# Snare.net
KiCad netlist of a schematic drawn in EAGLE
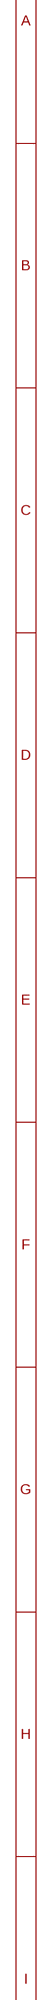
[diagram p0: schematic, sheet 1, part 1 of 2]
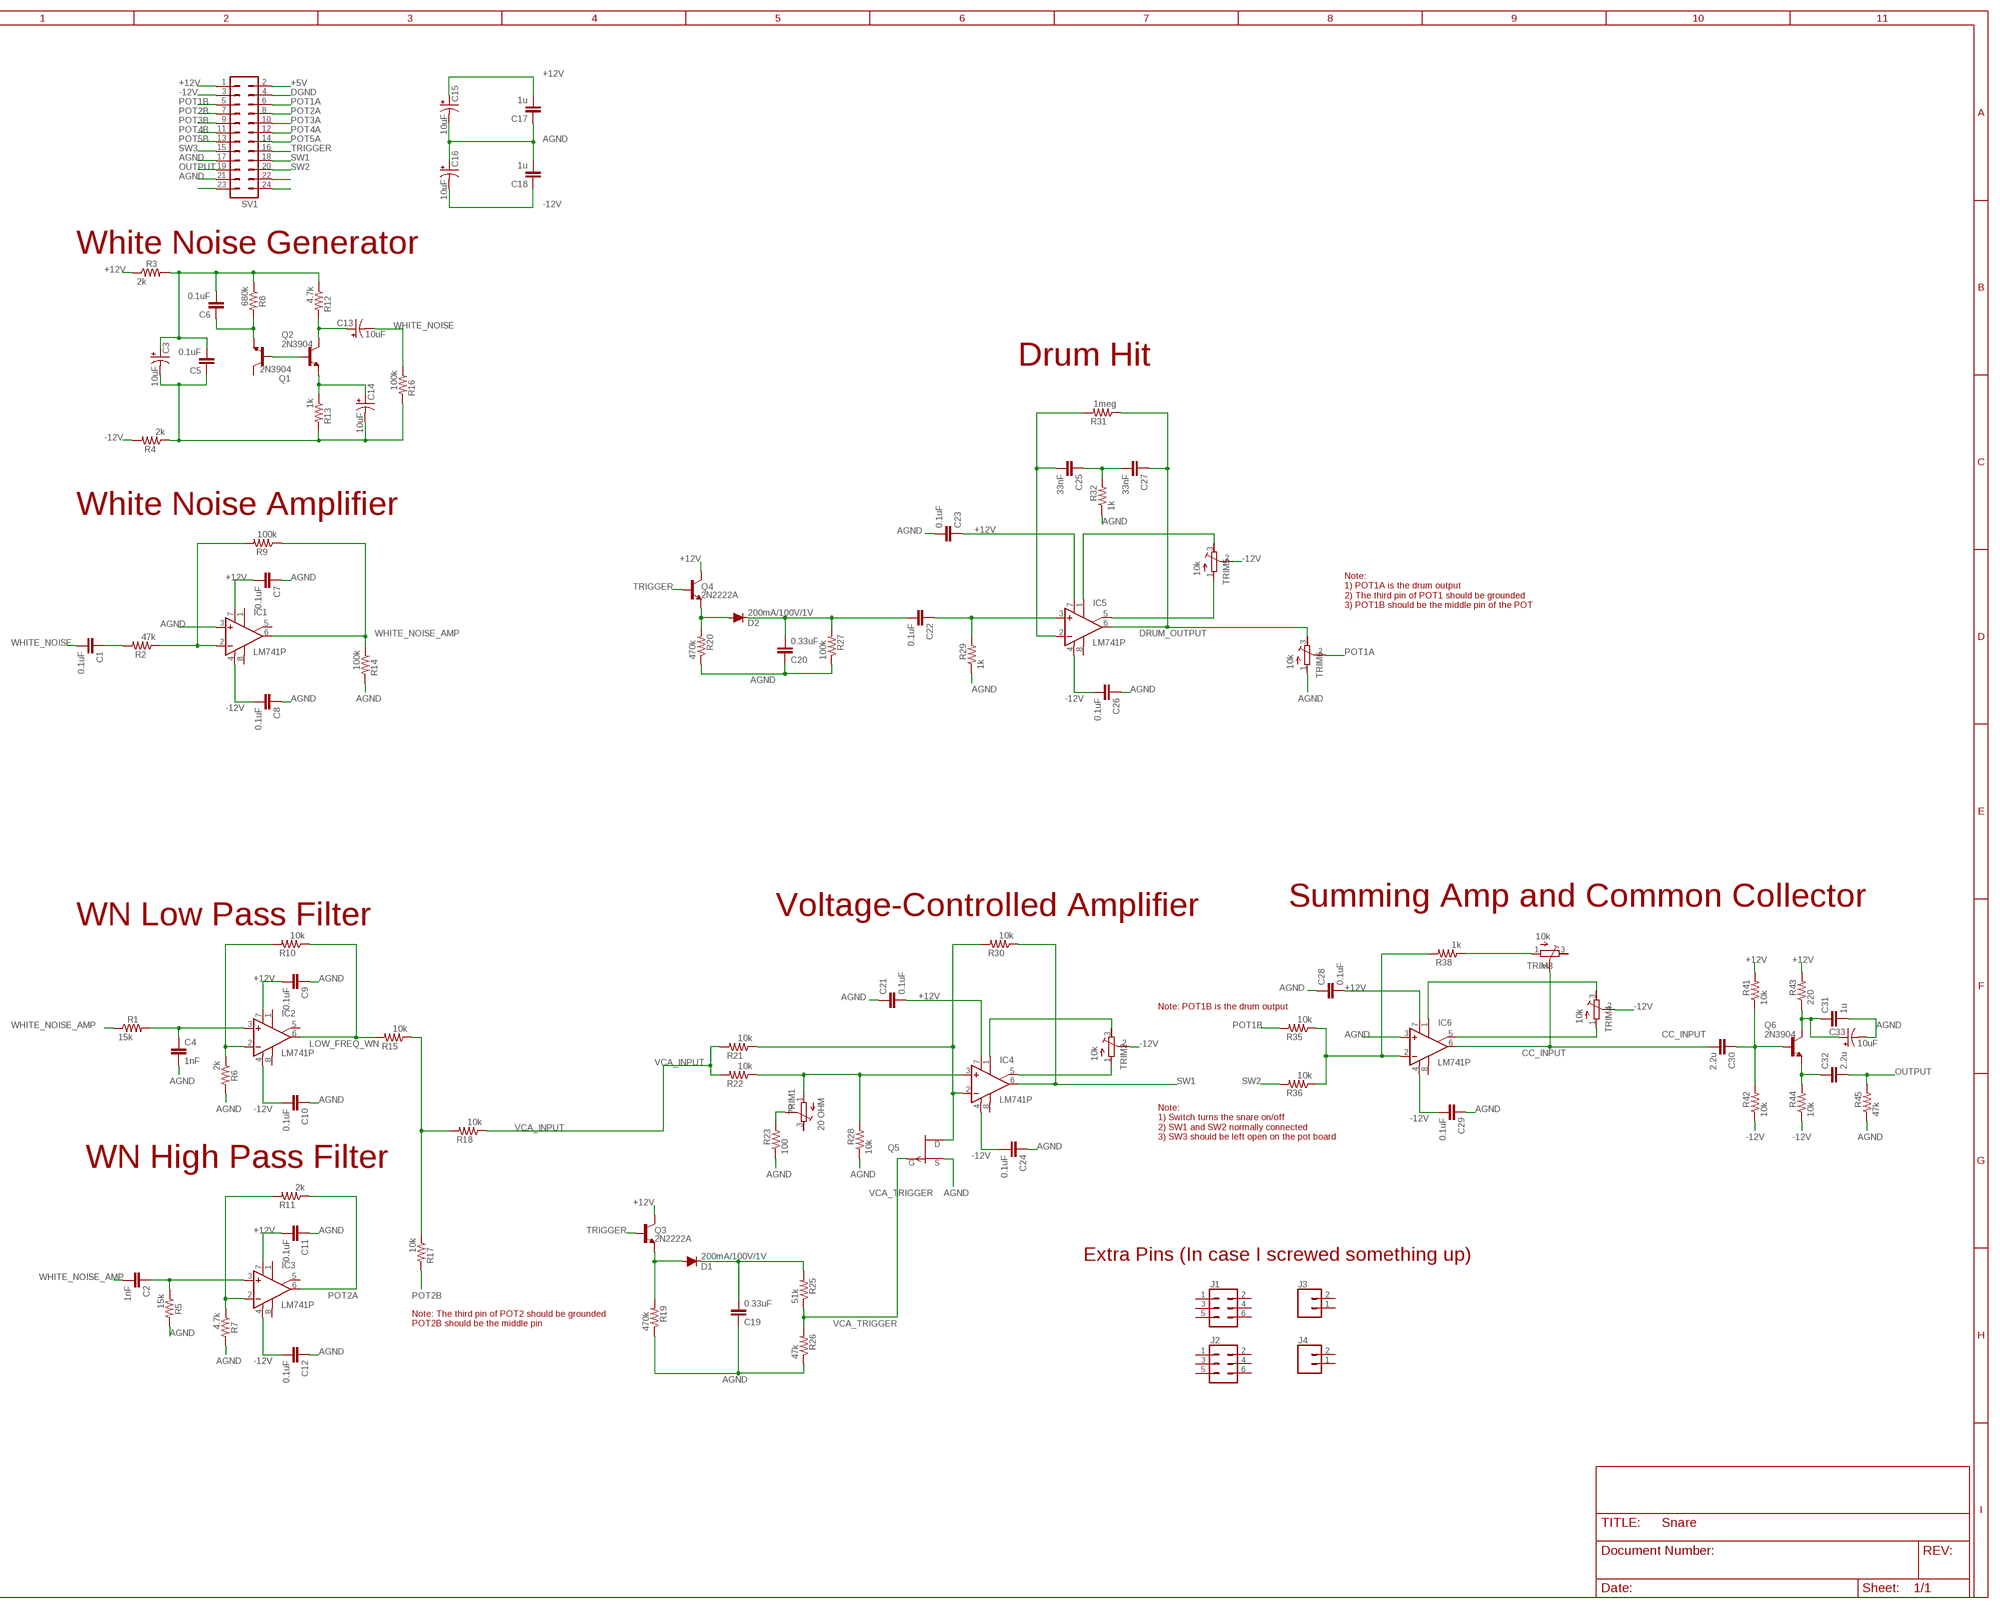
[diagram p1: schematic, sheet 1, part 2 of 2]

(export (version "E")
  (design (tool "Eeschema 10.0.6"))
  (components
    (comp (ref "C1")
      (value "0.1uF")
      (footprint "eagle-import:C050-024X044")
      (libsource (lib "eagle-import") (part "C-EU050-024X044"))
    )
    (comp (ref "C2")
      (value "1nF")
      (footprint "eagle-import:C050-024X044")
      (libsource (lib "eagle-import") (part "C-EU050-024X044"))
    )
    (comp (ref "C3")
      (value "10uF")
      (footprint "eagle-import:E2,5-6")
      (libsource (lib "eagle-import") (part "CPOL-USE2.5-6"))
    )
    (comp (ref "C4")
      (value "1nF")
      (footprint "eagle-import:C050-024X044")
      (libsource (lib "eagle-import") (part "C-EU050-024X044"))
    )
    (comp (ref "C5")
      (value "0.1uF")
      (footprint "eagle-import:C050-024X044")
      (libsource (lib "eagle-import") (part "C-EU050-024X044"))
    )
    (comp (ref "C6")
      (value "0.1uF")
      (footprint "eagle-import:C050-024X044")
      (libsource (lib "eagle-import") (part "C-EU050-024X044"))
    )
    (comp (ref "C7")
      (value "0.1uF")
      (footprint "eagle-import:C050-024X044")
      (libsource (lib "eagle-import") (part "C-EU050-024X044"))
    )
    (comp (ref "C8")
      (value "0.1uF")
      (footprint "eagle-import:C050-024X044")
      (libsource (lib "eagle-import") (part "C-EU050-024X044"))
    )
    (comp (ref "C9")
      (value "0.1uF")
      (footprint "eagle-import:C050-024X044")
      (libsource (lib "eagle-import") (part "C-EU050-024X044"))
    )
    (comp (ref "C10")
      (value "0.1uF")
      (footprint "eagle-import:C050-024X044")
      (libsource (lib "eagle-import") (part "C-EU050-024X044"))
    )
    (comp (ref "C11")
      (value "0.1uF")
      (footprint "eagle-import:C050-024X044")
      (libsource (lib "eagle-import") (part "C-EU050-024X044"))
    )
    (comp (ref "C12")
      (value "0.1uF")
      (footprint "eagle-import:C050-024X044")
      (libsource (lib "eagle-import") (part "C-EU050-024X044"))
    )
    (comp (ref "C13")
      (value "10uF")
      (footprint "eagle-import:E2,5-6")
      (libsource (lib "eagle-import") (part "CPOL-USE2.5-6"))
    )
    (comp (ref "C14")
      (value "10uF")
      (footprint "eagle-import:E2,5-6")
      (libsource (lib "eagle-import") (part "CPOL-USE2.5-6"))
    )
    (comp (ref "C15")
      (value "10uF")
      (footprint "eagle-import:E2,5-6")
      (libsource (lib "eagle-import") (part "CPOL-USE2.5-6"))
    )
    (comp (ref "C16")
      (value "10uF")
      (footprint "eagle-import:E2,5-6")
      (libsource (lib "eagle-import") (part "CPOL-USE2.5-6"))
    )
    (comp (ref "C17")
      (value "1u")
      (footprint "eagle-import:C050-024X044")
      (libsource (lib "eagle-import") (part "C-EU050-024X044"))
    )
    (comp (ref "C18")
      (value "1u")
      (footprint "eagle-import:C050-024X044")
      (libsource (lib "eagle-import") (part "C-EU050-024X044"))
    )
    (comp (ref "C19")
      (value "0.33uF")
      (footprint "eagle-import:C050-024X044")
      (libsource (lib "eagle-import") (part "C-EU050-024X044"))
    )
    (comp (ref "C20")
      (value "0.33uF")
      (footprint "eagle-import:C050-024X044")
      (libsource (lib "eagle-import") (part "C-EU050-024X044"))
    )
    (comp (ref "C21")
      (value "0.1uF")
      (footprint "eagle-import:C050-024X044")
      (libsource (lib "eagle-import") (part "C-EU050-024X044"))
    )
    (comp (ref "C22")
      (value "0.1uF")
      (footprint "eagle-import:C050-024X044")
      (libsource (lib "eagle-import") (part "C-EU050-024X044"))
    )
    (comp (ref "C23")
      (value "0.1uF")
      (footprint "eagle-import:C050-024X044")
      (libsource (lib "eagle-import") (part "C-EU050-024X044"))
    )
    (comp (ref "C24")
      (value "0.1uF")
      (footprint "eagle-import:C050-024X044")
      (libsource (lib "eagle-import") (part "C-EU050-024X044"))
    )
    (comp (ref "C25")
      (value "33nF")
      (footprint "eagle-import:C050-024X044")
      (libsource (lib "eagle-import") (part "C-EU050-024X044"))
    )
    (comp (ref "C26")
      (value "0.1uF")
      (footprint "eagle-import:C050-024X044")
      (libsource (lib "eagle-import") (part "C-EU050-024X044"))
    )
    (comp (ref "C27")
      (value "33nF")
      (footprint "eagle-import:C050-024X044")
      (libsource (lib "eagle-import") (part "C-EU050-024X044"))
    )
    (comp (ref "C28")
      (value "0.1uF")
      (footprint "eagle-import:C050-024X044")
      (libsource (lib "eagle-import") (part "C-EU050-024X044"))
    )
    (comp (ref "C29")
      (value "0.1uF")
      (footprint "eagle-import:C050-024X044")
      (libsource (lib "eagle-import") (part "C-EU050-024X044"))
    )
    (comp (ref "C30")
      (value "2.2u")
      (footprint "eagle-import:C050-024X044")
      (libsource (lib "eagle-import") (part "C-EU050-024X044"))
    )
    (comp (ref "C31")
      (value "1u")
      (footprint "eagle-import:C050-024X044")
      (libsource (lib "eagle-import") (part "C-EU050-024X044"))
    )
    (comp (ref "C32")
      (value "2.2u")
      (footprint "eagle-import:C050-024X044")
      (libsource (lib "eagle-import") (part "C-EU050-024X044"))
    )
    (comp (ref "C33")
      (value "10uF")
      (footprint "eagle-import:E2,5-6")
      (libsource (lib "eagle-import") (part "CPOL-USE2.5-6"))
    )
    (comp (ref "D1")
      (value "200mA/100V/1V")
      (footprint "eagle-import:DIODE-1N4148")
      (libsource (lib "eagle-import") (part "DIODE-1N4148"))
    )
    (comp (ref "D2")
      (value "200mA/100V/1V")
      (footprint "eagle-import:DIODE-1N4148")
      (libsource (lib "eagle-import") (part "DIODE-1N4148"))
    )
    (comp (ref "IC1")
      (value "LM741P")
      (footprint "eagle-import:DIL08")
      (libsource (lib "eagle-import") (part "741PLM"))
    )
    (comp (ref "IC2")
      (value "LM741P")
      (footprint "eagle-import:DIL08")
      (libsource (lib "eagle-import") (part "741PLM"))
    )
    (comp (ref "IC3")
      (value "LM741P")
      (footprint "eagle-import:DIL08")
      (libsource (lib "eagle-import") (part "741PLM"))
    )
    (comp (ref "IC4")
      (value "LM741P")
      (footprint "eagle-import:DIL08")
      (libsource (lib "eagle-import") (part "741PLM"))
    )
    (comp (ref "IC5")
      (value "LM741P")
      (footprint "eagle-import:DIL08")
      (libsource (lib "eagle-import") (part "741PLM"))
    )
    (comp (ref "IC6")
      (value "LM741P")
      (footprint "eagle-import:DIL08")
      (libsource (lib "eagle-import") (part "741PLM"))
    )
    (comp (ref "J1")
      (value "CONN_03X2NO_SILK")
      (footprint "eagle-import:2X3-NS")
      (libsource (lib "eagle-import") (part "CONN_03X2NO_SILK"))
    )
    (comp (ref "J2")
      (value "CONN_03X2NO_SILK")
      (footprint "eagle-import:2X3-NS")
      (libsource (lib "eagle-import") (part "CONN_03X2NO_SILK"))
    )
    (comp (ref "J3")
      (value "CONN_021X02_NO_SILK")
      (footprint "eagle-import:1X02_NO_SILK")
      (libsource (lib "eagle-import") (part "CONN_021X02_NO_SILK"))
    )
    (comp (ref "J4")
      (value "CONN_021X02_NO_SILK")
      (footprint "eagle-import:1X02_NO_SILK")
      (libsource (lib "eagle-import") (part "CONN_021X02_NO_SILK"))
    )
    (comp (ref "Q1")
      (value "2N3904")
      (footprint "eagle-import:TO92")
      (libsource (lib "eagle-import") (part "2N3904"))
    )
    (comp (ref "Q2")
      (value "2N3904")
      (footprint "eagle-import:TO92")
      (libsource (lib "eagle-import") (part "2N3904"))
    )
    (comp (ref "Q3")
      (value "2N2222A")
      (footprint "eagle-import:TO-92")
      (libsource (lib "eagle-import") (part "TRANS_NPN-P2N2222A"))
    )
    (comp (ref "Q4")
      (value "2N2222A")
      (footprint "eagle-import:TO-92")
      (libsource (lib "eagle-import") (part "TRANS_NPN-P2N2222A"))
    )
    (comp (ref "Q5")
      (value "J176")
      (footprint "eagle-import:TO-92")
      (libsource (lib "eagle-import") (part "J176"))
    )
    (comp (ref "Q6")
      (value "2N3904")
      (footprint "eagle-import:TO92")
      (libsource (lib "eagle-import") (part "2N3904"))
    )
    (comp (ref "R1")
      (value "15k")
      (footprint "eagle-import:0207_10")
      (libsource (lib "eagle-import") (part "R-US_0207/10"))
    )
    (comp (ref "R2")
      (value "47k")
      (footprint "eagle-import:0207_10")
      (libsource (lib "eagle-import") (part "R-US_0207/10"))
    )
    (comp (ref "R3")
      (value "2k")
      (footprint "eagle-import:0207_10")
      (libsource (lib "eagle-import") (part "R-US_0207/10"))
    )
    (comp (ref "R4")
      (value "2k")
      (footprint "eagle-import:0207_10")
      (libsource (lib "eagle-import") (part "R-US_0207/10"))
    )
    (comp (ref "R5")
      (value "15k")
      (footprint "eagle-import:0207_10")
      (libsource (lib "eagle-import") (part "R-US_0207/10"))
    )
    (comp (ref "R6")
      (value "2k")
      (footprint "eagle-import:0207_10")
      (libsource (lib "eagle-import") (part "R-US_0207/10"))
    )
    (comp (ref "R7")
      (value "4.7k")
      (footprint "eagle-import:0207_10")
      (libsource (lib "eagle-import") (part "R-US_0207/10"))
    )
    (comp (ref "R8")
      (value "680k")
      (footprint "eagle-import:0207_10")
      (libsource (lib "eagle-import") (part "R-US_0207/10"))
    )
    (comp (ref "R9")
      (value "100k")
      (footprint "eagle-import:0207_10")
      (libsource (lib "eagle-import") (part "R-US_0207/10"))
    )
    (comp (ref "R10")
      (value "10k")
      (footprint "eagle-import:0207_10")
      (libsource (lib "eagle-import") (part "R-US_0207/10"))
    )
    (comp (ref "R11")
      (value "2k")
      (footprint "eagle-import:0207_10")
      (libsource (lib "eagle-import") (part "R-US_0207/10"))
    )
    (comp (ref "R12")
      (value "4.7k")
      (footprint "eagle-import:0207_10")
      (libsource (lib "eagle-import") (part "R-US_0207/10"))
    )
    (comp (ref "R13")
      (value "1k")
      (footprint "eagle-import:0207_10")
      (libsource (lib "eagle-import") (part "R-US_0207/10"))
    )
    (comp (ref "R14")
      (value "100k")
      (footprint "eagle-import:0207_10")
      (libsource (lib "eagle-import") (part "R-US_0207/10"))
    )
    (comp (ref "R15")
      (value "10k")
      (footprint "eagle-import:0207_10")
      (libsource (lib "eagle-import") (part "R-US_0207/10"))
    )
    (comp (ref "R16")
      (value "100k")
      (footprint "eagle-import:0207_10")
      (libsource (lib "eagle-import") (part "R-US_0207/10"))
    )
    (comp (ref "R17")
      (value "10k")
      (footprint "eagle-import:0207_10")
      (libsource (lib "eagle-import") (part "R-US_0207/10"))
    )
    (comp (ref "R18")
      (value "10k")
      (footprint "eagle-import:0207_10")
      (libsource (lib "eagle-import") (part "R-US_0207/10"))
    )
    (comp (ref "R19")
      (value "470k")
      (footprint "eagle-import:0207_10")
      (libsource (lib "eagle-import") (part "R-US_0207/10"))
    )
    (comp (ref "R20")
      (value "470k")
      (footprint "eagle-import:0207_10")
      (libsource (lib "eagle-import") (part "R-US_0207/10"))
    )
    (comp (ref "R21")
      (value "10k")
      (footprint "eagle-import:0207_10")
      (libsource (lib "eagle-import") (part "R-US_0207/10"))
    )
    (comp (ref "R22")
      (value "10k")
      (footprint "eagle-import:0207_10")
      (libsource (lib "eagle-import") (part "R-US_0207/10"))
    )
    (comp (ref "R23")
      (value "100")
      (footprint "eagle-import:0207_10")
      (libsource (lib "eagle-import") (part "R-US_0207/10"))
    )
    (comp (ref "R25")
      (value "51k")
      (footprint "eagle-import:0207_10")
      (libsource (lib "eagle-import") (part "R-US_0207/10"))
    )
    (comp (ref "R26")
      (value "47k")
      (footprint "eagle-import:0207_10")
      (libsource (lib "eagle-import") (part "R-US_0207/10"))
    )
    (comp (ref "R27")
      (value "100k")
      (footprint "eagle-import:0207_10")
      (libsource (lib "eagle-import") (part "R-US_0207/10"))
    )
    (comp (ref "R28")
      (value "10k")
      (footprint "eagle-import:0207_10")
      (libsource (lib "eagle-import") (part "R-US_0207/10"))
    )
    (comp (ref "R29")
      (value "1k")
      (footprint "eagle-import:0207_10")
      (libsource (lib "eagle-import") (part "R-US_0207/10"))
    )
    (comp (ref "R30")
      (value "10k")
      (footprint "eagle-import:0207_10")
      (libsource (lib "eagle-import") (part "R-US_0207/10"))
    )
    (comp (ref "R31")
      (value "1meg")
      (footprint "eagle-import:0207_10")
      (libsource (lib "eagle-import") (part "R-US_0207/10"))
    )
    (comp (ref "R32")
      (value "1k")
      (footprint "eagle-import:0207_10")
      (libsource (lib "eagle-import") (part "R-US_0207/10"))
    )
    (comp (ref "R35")
      (value "10k")
      (footprint "eagle-import:0207_10")
      (libsource (lib "eagle-import") (part "R-US_0207/10"))
    )
    (comp (ref "R36")
      (value "10k")
      (footprint "eagle-import:0207_10")
      (libsource (lib "eagle-import") (part "R-US_0207/10"))
    )
    (comp (ref "R38")
      (value "1k")
      (footprint "eagle-import:0207_10")
      (libsource (lib "eagle-import") (part "R-US_0207/10"))
    )
    (comp (ref "R41")
      (value "10k")
      (footprint "eagle-import:0207_10")
      (libsource (lib "eagle-import") (part "R-US_0207/10"))
    )
    (comp (ref "R42")
      (value "10k")
      (footprint "eagle-import:0207_10")
      (libsource (lib "eagle-import") (part "R-US_0207/10"))
    )
    (comp (ref "R43")
      (value "220")
      (footprint "eagle-import:0207_10")
      (libsource (lib "eagle-import") (part "R-US_0207/10"))
    )
    (comp (ref "R44")
      (value "10k")
      (footprint "eagle-import:0207_10")
      (libsource (lib "eagle-import") (part "R-US_0207/10"))
    )
    (comp (ref "R45")
      (value "47k")
      (footprint "eagle-import:0207_10")
      (libsource (lib "eagle-import") (part "R-US_0207/10"))
    )
    (comp (ref "SV1")
      (value "MA12-2")
      (footprint "eagle-import:MA12-2")
      (libsource (lib "eagle-import") (part "MA12-2"))
    )
    (comp (ref "TRIM1")
      (value "20 OHM")
      (footprint "eagle-import:RTRIM64W")
      (libsource (lib "eagle-import") (part "R-TRIMM64W"))
    )
    (comp (ref "TRIM2")
      (value "10k")
      (footprint "eagle-import:RTRIM64W")
      (libsource (lib "eagle-import") (part "R-TRIMM64W"))
    )
    (comp (ref "TRIM3")
      (value "10k")
      (footprint "eagle-import:RTRIM64W")
      (libsource (lib "eagle-import") (part "R-TRIMM64W"))
    )
    (comp (ref "TRIM4")
      (value "10k")
      (footprint "eagle-import:RTRIM64W")
      (libsource (lib "eagle-import") (part "R-TRIMM64W"))
    )
    (comp (ref "TRIM5")
      (value "10k")
      (footprint "eagle-import:RTRIM64W")
      (libsource (lib "eagle-import") (part "R-TRIMM64W"))
    )
    (comp (ref "TRIM6")
      (value "10k")
      (footprint "eagle-import:RTRIM64W")
      (libsource (lib "eagle-import") (part "R-TRIMM64W"))
    )
  )
  (nets
    (net (code "1") (name "/+5V") (class "Default")
      (node (ref "SV1") (pin "2") (pinfunction "2_2") (pintype "passive"))
    )
    (net (code "2") (name "/+12V") (class "Default")
      (node (ref "C11") (pin "2") (pinfunction "2_2") (pintype "passive"))
      (node (ref "C15") (pin "+") (pinfunction "+_+") (pintype "passive"))
      (node (ref "C17") (pin "2") (pinfunction "2_2") (pintype "passive"))
      (node (ref "C21") (pin "2") (pinfunction "2_2") (pintype "passive"))
      (node (ref "C23") (pin "1") (pinfunction "1_1") (pintype "passive"))
      (node (ref "C28") (pin "2") (pinfunction "2_2") (pintype "passive"))
      (node (ref "C7") (pin "2") (pinfunction "2_2") (pintype "passive"))
      (node (ref "C9") (pin "2") (pinfunction "2_2") (pintype "passive"))
      (node (ref "IC1") (pin "7") (pinfunction "V+_7") (pintype "power_in"))
      (node (ref "IC2") (pin "7") (pinfunction "V+_7") (pintype "power_in"))
      (node (ref "IC3") (pin "7") (pinfunction "V+_7") (pintype "power_in"))
      (node (ref "IC4") (pin "7") (pinfunction "V+_7") (pintype "power_in"))
      (node (ref "IC5") (pin "7") (pinfunction "V+_7") (pintype "power_in"))
      (node (ref "IC6") (pin "7") (pinfunction "V+_7") (pintype "power_in"))
      (node (ref "Q3") (pin "1") (pinfunction "C_1") (pintype "passive"))
      (node (ref "Q4") (pin "1") (pinfunction "C_1") (pintype "passive"))
      (node (ref "R3") (pin "1") (pinfunction "1_1") (pintype "passive"))
      (node (ref "R41") (pin "2") (pinfunction "2_2") (pintype "passive"))
      (node (ref "R43") (pin "2") (pinfunction "2_2") (pintype "passive"))
      (node (ref "SV1") (pin "1") (pinfunction "1_1") (pintype "passive"))
    )
    (net (code "3") (name "/-12V") (class "Default")
      (node (ref "C10") (pin "2") (pinfunction "2_2") (pintype "passive"))
      (node (ref "C12") (pin "2") (pinfunction "2_2") (pintype "passive"))
      (node (ref "C16") (pin "-") (pinfunction "-_-") (pintype "passive"))
      (node (ref "C18") (pin "1") (pinfunction "1_1") (pintype "passive"))
      (node (ref "C24") (pin "2") (pinfunction "2_2") (pintype "passive"))
      (node (ref "C26") (pin "2") (pinfunction "2_2") (pintype "passive"))
      (node (ref "C29") (pin "2") (pinfunction "2_2") (pintype "passive"))
      (node (ref "C8") (pin "2") (pinfunction "2_2") (pintype "passive"))
      (node (ref "IC1") (pin "4") (pinfunction "V-_4") (pintype "power_in"))
      (node (ref "IC2") (pin "4") (pinfunction "V-_4") (pintype "power_in"))
      (node (ref "IC3") (pin "4") (pinfunction "V-_4") (pintype "power_in"))
      (node (ref "IC4") (pin "4") (pinfunction "V-_4") (pintype "power_in"))
      (node (ref "IC5") (pin "4") (pinfunction "V-_4") (pintype "power_in"))
      (node (ref "IC6") (pin "4") (pinfunction "V-_4") (pintype "power_in"))
      (node (ref "R4") (pin "2") (pinfunction "2_2") (pintype "passive"))
      (node (ref "R42") (pin "1") (pinfunction "1_1") (pintype "passive"))
      (node (ref "R44") (pin "1") (pinfunction "1_1") (pintype "passive"))
      (node (ref "SV1") (pin "3") (pinfunction "3_3") (pintype "passive"))
      (node (ref "TRIM2") (pin "2") (pinfunction "S_2") (pintype "passive"))
      (node (ref "TRIM4") (pin "2") (pinfunction "S_2") (pintype "passive"))
      (node (ref "TRIM5") (pin "2") (pinfunction "S_2") (pintype "passive"))
    )
    (net (code "4") (name "/AGND") (class "Default")
      (node (ref "C10") (pin "1") (pinfunction "1_1") (pintype "passive"))
      (node (ref "C11") (pin "1") (pinfunction "1_1") (pintype "passive"))
      (node (ref "C12") (pin "1") (pinfunction "1_1") (pintype "passive"))
      (node (ref "C15") (pin "-") (pinfunction "-_-") (pintype "passive"))
      (node (ref "C16") (pin "+") (pinfunction "+_+") (pintype "passive"))
      (node (ref "C17") (pin "1") (pinfunction "1_1") (pintype "passive"))
      (node (ref "C18") (pin "2") (pinfunction "2_2") (pintype "passive"))
      (node (ref "C19") (pin "1") (pinfunction "1_1") (pintype "passive"))
      (node (ref "C20") (pin "1") (pinfunction "1_1") (pintype "passive"))
      (node (ref "C21") (pin "1") (pinfunction "1_1") (pintype "passive"))
      (node (ref "C23") (pin "2") (pinfunction "2_2") (pintype "passive"))
      (node (ref "C24") (pin "1") (pinfunction "1_1") (pintype "passive"))
      (node (ref "C26") (pin "1") (pinfunction "1_1") (pintype "passive"))
      (node (ref "C28") (pin "1") (pinfunction "1_1") (pintype "passive"))
      (node (ref "C29") (pin "1") (pinfunction "1_1") (pintype "passive"))
      (node (ref "C31") (pin "2") (pinfunction "2_2") (pintype "passive"))
      (node (ref "C33") (pin "-") (pinfunction "-_-") (pintype "passive"))
      (node (ref "C4") (pin "2") (pinfunction "2_2") (pintype "passive"))
      (node (ref "C7") (pin "1") (pinfunction "1_1") (pintype "passive"))
      (node (ref "C8") (pin "1") (pinfunction "1_1") (pintype "passive"))
      (node (ref "C9") (pin "1") (pinfunction "1_1") (pintype "passive"))
      (node (ref "IC1") (pin "3") (pinfunction "+IN_3") (pintype "input"))
      (node (ref "IC6") (pin "3") (pinfunction "+IN_3") (pintype "input"))
      (node (ref "Q5") (pin "3") (pinfunction "S_3") (pintype "passive"))
      (node (ref "R14") (pin "2") (pinfunction "2_2") (pintype "passive"))
      (node (ref "R19") (pin "1") (pinfunction "1_1") (pintype "passive"))
      (node (ref "R20") (pin "1") (pinfunction "1_1") (pintype "passive"))
      (node (ref "R23") (pin "1") (pinfunction "1_1") (pintype "passive"))
      (node (ref "R26") (pin "1") (pinfunction "1_1") (pintype "passive"))
      (node (ref "R27") (pin "1") (pinfunction "1_1") (pintype "passive"))
      (node (ref "R28") (pin "1") (pinfunction "1_1") (pintype "passive"))
      (node (ref "R29") (pin "1") (pinfunction "1_1") (pintype "passive"))
      (node (ref "R32") (pin "1") (pinfunction "1_1") (pintype "passive"))
      (node (ref "R45") (pin "1") (pinfunction "1_1") (pintype "passive"))
      (node (ref "R5") (pin "2") (pinfunction "2_2") (pintype "passive"))
      (node (ref "R6") (pin "2") (pinfunction "2_2") (pintype "passive"))
      (node (ref "R7") (pin "2") (pinfunction "2_2") (pintype "passive"))
      (node (ref "SV1") (pin "17") (pinfunction "17_17") (pintype "passive"))
      (node (ref "SV1") (pin "21") (pinfunction "21_21") (pintype "passive"))
      (node (ref "TRIM6") (pin "1") (pinfunction "A_1") (pintype "passive"))
    )
    (net (code "5") (name "/CC_INPUT") (class "Default")
      (node (ref "C30") (pin "2") (pinfunction "2_2") (pintype "passive"))
      (node (ref "IC6") (pin "6") (pinfunction "OUT_6") (pintype "output"))
      (node (ref "TRIM3") (pin "2") (pinfunction "S_2") (pintype "passive"))
    )
    (net (code "6") (name "/DGND") (class "Default")
      (node (ref "SV1") (pin "4") (pinfunction "4_4") (pintype "passive"))
    )
    (net (code "7") (name "/DRUM_OUTPUT") (class "Default")
      (node (ref "C27") (pin "1") (pinfunction "1_1") (pintype "passive"))
      (node (ref "IC5") (pin "6") (pinfunction "OUT_6") (pintype "output"))
      (node (ref "R31") (pin "1") (pinfunction "1_1") (pintype "passive"))
      (node (ref "TRIM6") (pin "3") (pinfunction "E_3") (pintype "passive"))
    )
    (net (code "8") (name "/LOW_FREQ_WN") (class "Default")
      (node (ref "IC2") (pin "6") (pinfunction "OUT_6") (pintype "output"))
      (node (ref "R10") (pin "1") (pinfunction "1_1") (pintype "passive"))
      (node (ref "R15") (pin "2") (pinfunction "2_2") (pintype "passive"))
    )
    (net (code "9") (name "/OUTPUT") (class "Default")
      (node (ref "C32") (pin "2") (pinfunction "2_2") (pintype "passive"))
      (node (ref "R45") (pin "2") (pinfunction "2_2") (pintype "passive"))
      (node (ref "SV1") (pin "19") (pinfunction "19_19") (pintype "passive"))
    )
    (net (code "10") (name "/POT1A") (class "Default")
      (node (ref "SV1") (pin "6") (pinfunction "6_6") (pintype "passive"))
      (node (ref "TRIM6") (pin "2") (pinfunction "S_2") (pintype "passive"))
    )
    (net (code "11") (name "/POT1B") (class "Default")
      (node (ref "R35") (pin "2") (pinfunction "2_2") (pintype "passive"))
      (node (ref "SV1") (pin "5") (pinfunction "5_5") (pintype "passive"))
    )
    (net (code "12") (name "/POT2A") (class "Default")
      (node (ref "IC3") (pin "6") (pinfunction "OUT_6") (pintype "output"))
      (node (ref "R11") (pin "1") (pinfunction "1_1") (pintype "passive"))
      (node (ref "SV1") (pin "8") (pinfunction "8_8") (pintype "passive"))
    )
    (net (code "13") (name "/POT2B") (class "Default")
      (node (ref "R17") (pin "2") (pinfunction "2_2") (pintype "passive"))
      (node (ref "SV1") (pin "7") (pinfunction "7_7") (pintype "passive"))
    )
    (net (code "14") (name "/POT3A") (class "Default")
      (node (ref "SV1") (pin "10") (pinfunction "10_10") (pintype "passive"))
    )
    (net (code "15") (name "/POT3B") (class "Default")
      (node (ref "SV1") (pin "9") (pinfunction "9_9") (pintype "passive"))
    )
    (net (code "16") (name "/POT4A") (class "Default")
      (node (ref "SV1") (pin "12") (pinfunction "12_12") (pintype "passive"))
    )
    (net (code "17") (name "/POT4B") (class "Default")
      (node (ref "SV1") (pin "11") (pinfunction "11_11") (pintype "passive"))
    )
    (net (code "18") (name "/POT5A") (class "Default")
      (node (ref "SV1") (pin "14") (pinfunction "14_14") (pintype "passive"))
    )
    (net (code "19") (name "/POT5B") (class "Default")
      (node (ref "SV1") (pin "13") (pinfunction "13_13") (pintype "passive"))
    )
    (net (code "20") (name "/SW1") (class "Default")
      (node (ref "IC4") (pin "6") (pinfunction "OUT_6") (pintype "output"))
      (node (ref "R30") (pin "1") (pinfunction "1_1") (pintype "passive"))
      (node (ref "SV1") (pin "18") (pinfunction "18_18") (pintype "passive"))
    )
    (net (code "21") (name "/SW2") (class "Default")
      (node (ref "R36") (pin "2") (pinfunction "2_2") (pintype "passive"))
      (node (ref "SV1") (pin "20") (pinfunction "20_20") (pintype "passive"))
    )
    (net (code "22") (name "/SW3") (class "Default")
      (node (ref "SV1") (pin "15") (pinfunction "15_15") (pintype "passive"))
    )
    (net (code "23") (name "/TRIGGER") (class "Default")
      (node (ref "Q3") (pin "2") (pinfunction "B_2") (pintype "passive"))
      (node (ref "Q4") (pin "2") (pinfunction "B_2") (pintype "passive"))
      (node (ref "SV1") (pin "16") (pinfunction "16_16") (pintype "passive"))
    )
    (net (code "24") (name "/VCA_INPUT") (class "Default")
      (node (ref "R18") (pin "1") (pinfunction "1_1") (pintype "passive"))
      (node (ref "R21") (pin "2") (pinfunction "2_2") (pintype "passive"))
      (node (ref "R22") (pin "2") (pinfunction "2_2") (pintype "passive"))
    )
    (net (code "25") (name "/VCA_TRIGGER") (class "Default")
      (node (ref "Q5") (pin "2") (pinfunction "G_2") (pintype "passive"))
      (node (ref "R25") (pin "1") (pinfunction "1_1") (pintype "passive"))
      (node (ref "R26") (pin "2") (pinfunction "2_2") (pintype "passive"))
    )
    (net (code "26") (name "/WHITE_NOISE") (class "Default")
      (node (ref "C1") (pin "2") (pinfunction "2_2") (pintype "passive"))
      (node (ref "C13") (pin "-") (pinfunction "-_-") (pintype "passive"))
      (node (ref "R16") (pin "1") (pinfunction "1_1") (pintype "passive"))
    )
    (net (code "27") (name "/WHITE_NOISE_AMP") (class "Default")
      (node (ref "C2") (pin "2") (pinfunction "2_2") (pintype "passive"))
      (node (ref "IC1") (pin "6") (pinfunction "OUT_6") (pintype "output"))
      (node (ref "R1") (pin "1") (pinfunction "1_1") (pintype "passive"))
      (node (ref "R14") (pin "1") (pinfunction "1_1") (pintype "passive"))
      (node (ref "R9") (pin "1") (pinfunction "1_1") (pintype "passive"))
    )
    (net (code "28") (name "Net-(C1-Pad1)") (class "Default")
      (node (ref "C1") (pin "1") (pinfunction "1_1") (pintype "passive"))
      (node (ref "R2") (pin "2") (pinfunction "2_2") (pintype "passive"))
    )
    (net (code "29") (name "Net-(C3-Pad+)") (class "Default")
      (node (ref "C3") (pin "+") (pinfunction "+_+") (pintype "passive"))
      (node (ref "C5") (pin "2") (pinfunction "2_2") (pintype "passive"))
      (node (ref "C6") (pin "2") (pinfunction "2_2") (pintype "passive"))
      (node (ref "R12") (pin "1") (pinfunction "1_1") (pintype "passive"))
      (node (ref "R3") (pin "2") (pinfunction "2_2") (pintype "passive"))
      (node (ref "R8") (pin "1") (pinfunction "1_1") (pintype "passive"))
    )
    (net (code "30") (name "Net-(C14-Pad-)") (class "Default")
      (node (ref "C14") (pin "-") (pinfunction "-_-") (pintype "passive"))
      (node (ref "C3") (pin "-") (pinfunction "-_-") (pintype "passive"))
      (node (ref "C5") (pin "1") (pinfunction "1_1") (pintype "passive"))
      (node (ref "R13") (pin "2") (pinfunction "2_2") (pintype "passive"))
      (node (ref "R16") (pin "2") (pinfunction "2_2") (pintype "passive"))
      (node (ref "R4") (pin "1") (pinfunction "1_1") (pintype "passive"))
    )
    (net (code "31") (name "Net-(C19-Pad2)") (class "Default")
      (node (ref "C19") (pin "2") (pinfunction "2_2") (pintype "passive"))
      (node (ref "D1") (pin "C") (pinfunction "C_C") (pintype "passive"))
      (node (ref "R25") (pin "2") (pinfunction "2_2") (pintype "passive"))
    )
    (net (code "32") (name "Net-(C20-Pad2)") (class "Default")
      (node (ref "C20") (pin "2") (pinfunction "2_2") (pintype "passive"))
      (node (ref "C22") (pin "2") (pinfunction "2_2") (pintype "passive"))
      (node (ref "D2") (pin "C") (pinfunction "C_C") (pintype "passive"))
      (node (ref "R27") (pin "2") (pinfunction "2_2") (pintype "passive"))
    )
    (net (code "33") (name "Net-(C25-Pad1)") (class "Default")
      (node (ref "C25") (pin "1") (pinfunction "1_1") (pintype "passive"))
      (node (ref "C27") (pin "2") (pinfunction "2_2") (pintype "passive"))
      (node (ref "R32") (pin "2") (pinfunction "2_2") (pintype "passive"))
    )
    (net (code "34") (name "Net-(IC1--IN)") (class "Default")
      (node (ref "IC1") (pin "2") (pinfunction "-IN_2") (pintype "input"))
      (node (ref "R2") (pin "1") (pinfunction "1_1") (pintype "passive"))
      (node (ref "R9") (pin "2") (pinfunction "2_2") (pintype "passive"))
    )
    (net (code "35") (name "Net-(IC2-+IN)") (class "Default")
      (node (ref "C4") (pin "1") (pinfunction "1_1") (pintype "passive"))
      (node (ref "IC2") (pin "3") (pinfunction "+IN_3") (pintype "input"))
      (node (ref "R1") (pin "2") (pinfunction "2_2") (pintype "passive"))
    )
    (net (code "36") (name "Net-(IC2--IN)") (class "Default")
      (node (ref "IC2") (pin "2") (pinfunction "-IN_2") (pintype "input"))
      (node (ref "R10") (pin "2") (pinfunction "2_2") (pintype "passive"))
      (node (ref "R6") (pin "1") (pinfunction "1_1") (pintype "passive"))
    )
    (net (code "37") (name "Net-(IC3-+IN)") (class "Default")
      (node (ref "C2") (pin "1") (pinfunction "1_1") (pintype "passive"))
      (node (ref "IC3") (pin "3") (pinfunction "+IN_3") (pintype "input"))
      (node (ref "R5") (pin "1") (pinfunction "1_1") (pintype "passive"))
    )
    (net (code "38") (name "Net-(IC3--IN)") (class "Default")
      (node (ref "IC3") (pin "2") (pinfunction "-IN_2") (pintype "input"))
      (node (ref "R11") (pin "2") (pinfunction "2_2") (pintype "passive"))
      (node (ref "R7") (pin "1") (pinfunction "1_1") (pintype "passive"))
    )
    (net (code "39") (name "Net-(IC4-+IN)") (class "Default")
      (node (ref "IC4") (pin "3") (pinfunction "+IN_3") (pintype "input"))
      (node (ref "R22") (pin "1") (pinfunction "1_1") (pintype "passive"))
      (node (ref "R28") (pin "2") (pinfunction "2_2") (pintype "passive"))
      (node (ref "TRIM1") (pin "1") (pinfunction "A_1") (pintype "passive"))
    )
    (net (code "40") (name "Net-(IC4--IN)") (class "Default")
      (node (ref "IC4") (pin "2") (pinfunction "-IN_2") (pintype "input"))
      (node (ref "Q5") (pin "1") (pinfunction "D_1") (pintype "passive"))
      (node (ref "R21") (pin "1") (pinfunction "1_1") (pintype "passive"))
      (node (ref "R30") (pin "2") (pinfunction "2_2") (pintype "passive"))
    )
    (net (code "41") (name "Net-(IC4-ON1)") (class "Default")
      (node (ref "IC4") (pin "1") (pinfunction "ON1_1") (pintype "passive"))
      (node (ref "TRIM2") (pin "3") (pinfunction "E_3") (pintype "passive"))
    )
    (net (code "42") (name "Net-(IC4-ON2)") (class "Default")
      (node (ref "IC4") (pin "5") (pinfunction "ON2_5") (pintype "passive"))
      (node (ref "TRIM2") (pin "1") (pinfunction "A_1") (pintype "passive"))
    )
    (net (code "43") (name "Net-(IC5-+IN)") (class "Default")
      (node (ref "C22") (pin "1") (pinfunction "1_1") (pintype "passive"))
      (node (ref "IC5") (pin "3") (pinfunction "+IN_3") (pintype "input"))
      (node (ref "R29") (pin "2") (pinfunction "2_2") (pintype "passive"))
    )
    (net (code "44") (name "Net-(IC5--IN)") (class "Default")
      (node (ref "C25") (pin "2") (pinfunction "2_2") (pintype "passive"))
      (node (ref "IC5") (pin "2") (pinfunction "-IN_2") (pintype "input"))
      (node (ref "R31") (pin "2") (pinfunction "2_2") (pintype "passive"))
    )
    (net (code "45") (name "Net-(IC5-ON1)") (class "Default")
      (node (ref "IC5") (pin "1") (pinfunction "ON1_1") (pintype "passive"))
      (node (ref "TRIM5") (pin "3") (pinfunction "E_3") (pintype "passive"))
    )
    (net (code "46") (name "Net-(IC5-ON2)") (class "Default")
      (node (ref "IC5") (pin "5") (pinfunction "ON2_5") (pintype "passive"))
      (node (ref "TRIM5") (pin "1") (pinfunction "A_1") (pintype "passive"))
    )
    (net (code "47") (name "Net-(IC6--IN)") (class "Default")
      (node (ref "IC6") (pin "2") (pinfunction "-IN_2") (pintype "input"))
      (node (ref "R35") (pin "1") (pinfunction "1_1") (pintype "passive"))
      (node (ref "R36") (pin "1") (pinfunction "1_1") (pintype "passive"))
      (node (ref "R38") (pin "2") (pinfunction "2_2") (pintype "passive"))
    )
    (net (code "48") (name "Net-(IC6-ON1)") (class "Default")
      (node (ref "IC6") (pin "1") (pinfunction "ON1_1") (pintype "passive"))
      (node (ref "TRIM4") (pin "3") (pinfunction "E_3") (pintype "passive"))
    )
    (net (code "49") (name "Net-(IC6-ON2)") (class "Default")
      (node (ref "IC6") (pin "5") (pinfunction "ON2_5") (pintype "passive"))
      (node (ref "TRIM4") (pin "1") (pinfunction "A_1") (pintype "passive"))
    )
    (net (code "50") (name "Net-(Q1-B)") (class "Default")
      (node (ref "Q1") (pin "2") (pinfunction "B_2") (pintype "passive"))
      (node (ref "Q2") (pin "2") (pinfunction "B_2") (pintype "passive"))
    )
    (net (code "51") (name "Net-(Q1-E)") (class "Default")
      (node (ref "C6") (pin "1") (pinfunction "1_1") (pintype "passive"))
      (node (ref "Q1") (pin "3") (pinfunction "E_3") (pintype "passive"))
      (node (ref "R8") (pin "2") (pinfunction "2_2") (pintype "passive"))
    )
    (net (code "52") (name "Net-(Q2-C)") (class "Default")
      (node (ref "C13") (pin "+") (pinfunction "+_+") (pintype "passive"))
      (node (ref "Q2") (pin "1") (pinfunction "C_1") (pintype "passive"))
      (node (ref "R12") (pin "2") (pinfunction "2_2") (pintype "passive"))
    )
    (net (code "53") (name "Net-(Q2-E)") (class "Default")
      (node (ref "C14") (pin "+") (pinfunction "+_+") (pintype "passive"))
      (node (ref "Q2") (pin "3") (pinfunction "E_3") (pintype "passive"))
      (node (ref "R13") (pin "1") (pinfunction "1_1") (pintype "passive"))
    )
    (net (code "54") (name "Net-(Q3-E)") (class "Default")
      (node (ref "D1") (pin "A") (pinfunction "A_A") (pintype "passive"))
      (node (ref "Q3") (pin "3") (pinfunction "E_3") (pintype "passive"))
      (node (ref "R19") (pin "2") (pinfunction "2_2") (pintype "passive"))
    )
    (net (code "55") (name "Net-(Q4-E)") (class "Default")
      (node (ref "D2") (pin "A") (pinfunction "A_A") (pintype "passive"))
      (node (ref "Q4") (pin "3") (pinfunction "E_3") (pintype "passive"))
      (node (ref "R20") (pin "2") (pinfunction "2_2") (pintype "passive"))
    )
    (net (code "56") (name "Net-(Q6-B)") (class "Default")
      (node (ref "C30") (pin "1") (pinfunction "1_1") (pintype "passive"))
      (node (ref "Q6") (pin "2") (pinfunction "B_2") (pintype "passive"))
      (node (ref "R41") (pin "1") (pinfunction "1_1") (pintype "passive"))
      (node (ref "R42") (pin "2") (pinfunction "2_2") (pintype "passive"))
    )
    (net (code "57") (name "Net-(Q6-C)") (class "Default")
      (node (ref "C31") (pin "1") (pinfunction "1_1") (pintype "passive"))
      (node (ref "C33") (pin "+") (pinfunction "+_+") (pintype "passive"))
      (node (ref "Q6") (pin "1") (pinfunction "C_1") (pintype "passive"))
      (node (ref "R43") (pin "1") (pinfunction "1_1") (pintype "passive"))
    )
    (net (code "58") (name "Net-(Q6-E)") (class "Default")
      (node (ref "C32") (pin "1") (pinfunction "1_1") (pintype "passive"))
      (node (ref "Q6") (pin "3") (pinfunction "E_3") (pintype "passive"))
      (node (ref "R44") (pin "2") (pinfunction "2_2") (pintype "passive"))
    )
    (net (code "59") (name "Net-(R15-Pad1)") (class "Default")
      (node (ref "R15") (pin "1") (pinfunction "1_1") (pintype "passive"))
      (node (ref "R17") (pin "1") (pinfunction "1_1") (pintype "passive"))
      (node (ref "R18") (pin "2") (pinfunction "2_2") (pintype "passive"))
    )
    (net (code "60") (name "Net-(TRIM1-S)") (class "Default")
      (node (ref "R23") (pin "2") (pinfunction "2_2") (pintype "passive"))
      (node (ref "TRIM1") (pin "2") (pinfunction "S_2") (pintype "passive"))
    )
    (net (code "61") (name "Net-(TRIM3-A)") (class "Default")
      (node (ref "R38") (pin "1") (pinfunction "1_1") (pintype "passive"))
      (node (ref "TRIM3") (pin "1") (pinfunction "A_1") (pintype "passive"))
    )
    (net (code "62") (name "unconnected-(IC1-ON1-Pad1)") (class "Default")
      (node (ref "IC1") (pin "1") (pinfunction "ON1_1") (pintype "passive"))
    )
    (net (code "63") (name "unconnected-(IC1-ON2-Pad5)") (class "Default")
      (node (ref "IC1") (pin "5") (pinfunction "ON2_5") (pintype "passive"))
    )
    (net (code "64") (name "unconnected-(IC1-OPT-Pad8)") (class "Default")
      (node (ref "IC1") (pin "8") (pinfunction "OPT_8") (pintype "passive"))
    )
    (net (code "65") (name "unconnected-(IC2-ON1-Pad1)") (class "Default")
      (node (ref "IC2") (pin "1") (pinfunction "ON1_1") (pintype "passive"))
    )
    (net (code "66") (name "unconnected-(IC2-ON2-Pad5)") (class "Default")
      (node (ref "IC2") (pin "5") (pinfunction "ON2_5") (pintype "passive"))
    )
    (net (code "67") (name "unconnected-(IC2-OPT-Pad8)") (class "Default")
      (node (ref "IC2") (pin "8") (pinfunction "OPT_8") (pintype "passive"))
    )
    (net (code "68") (name "unconnected-(IC3-ON1-Pad1)") (class "Default")
      (node (ref "IC3") (pin "1") (pinfunction "ON1_1") (pintype "passive"))
    )
    (net (code "69") (name "unconnected-(IC3-ON2-Pad5)") (class "Default")
      (node (ref "IC3") (pin "5") (pinfunction "ON2_5") (pintype "passive"))
    )
    (net (code "70") (name "unconnected-(IC3-OPT-Pad8)") (class "Default")
      (node (ref "IC3") (pin "8") (pinfunction "OPT_8") (pintype "passive"))
    )
    (net (code "71") (name "unconnected-(IC4-OPT-Pad8)") (class "Default")
      (node (ref "IC4") (pin "8") (pinfunction "OPT_8") (pintype "passive"))
    )
    (net (code "72") (name "unconnected-(IC5-OPT-Pad8)") (class "Default")
      (node (ref "IC5") (pin "8") (pinfunction "OPT_8") (pintype "passive"))
    )
    (net (code "73") (name "unconnected-(IC6-OPT-Pad8)") (class "Default")
      (node (ref "IC6") (pin "8") (pinfunction "OPT_8") (pintype "passive"))
    )
    (net (code "74") (name "unconnected-(J1-Pad1)") (class "Default")
      (node (ref "J1") (pin "1") (pinfunction "1_1") (pintype "bidirectional"))
    )
    (net (code "75") (name "unconnected-(J1-Pad2)") (class "Default")
      (node (ref "J1") (pin "2") (pinfunction "2_2") (pintype "bidirectional"))
    )
    (net (code "76") (name "unconnected-(J1-Pad3)") (class "Default")
      (node (ref "J1") (pin "3") (pinfunction "3_3") (pintype "bidirectional"))
    )
    (net (code "77") (name "unconnected-(J1-Pad4)") (class "Default")
      (node (ref "J1") (pin "4") (pinfunction "4_4") (pintype "bidirectional"))
    )
    (net (code "78") (name "unconnected-(J1-Pad5)") (class "Default")
      (node (ref "J1") (pin "5") (pinfunction "5_5") (pintype "bidirectional"))
    )
    (net (code "79") (name "unconnected-(J1-Pad6)") (class "Default")
      (node (ref "J1") (pin "6") (pinfunction "6_6") (pintype "bidirectional"))
    )
    (net (code "80") (name "unconnected-(J2-Pad1)") (class "Default")
      (node (ref "J2") (pin "1") (pinfunction "1_1") (pintype "bidirectional"))
    )
    (net (code "81") (name "unconnected-(J2-Pad2)") (class "Default")
      (node (ref "J2") (pin "2") (pinfunction "2_2") (pintype "bidirectional"))
    )
    (net (code "82") (name "unconnected-(J2-Pad3)") (class "Default")
      (node (ref "J2") (pin "3") (pinfunction "3_3") (pintype "bidirectional"))
    )
    (net (code "83") (name "unconnected-(J2-Pad4)") (class "Default")
      (node (ref "J2") (pin "4") (pinfunction "4_4") (pintype "bidirectional"))
    )
    (net (code "84") (name "unconnected-(J2-Pad5)") (class "Default")
      (node (ref "J2") (pin "5") (pinfunction "5_5") (pintype "bidirectional"))
    )
    (net (code "85") (name "unconnected-(J2-Pad6)") (class "Default")
      (node (ref "J2") (pin "6") (pinfunction "6_6") (pintype "bidirectional"))
    )
    (net (code "86") (name "unconnected-(J3-Pad1)") (class "Default")
      (node (ref "J3") (pin "1") (pinfunction "1_1") (pintype "passive"))
    )
    (net (code "87") (name "unconnected-(J3-Pad2)") (class "Default")
      (node (ref "J3") (pin "2") (pinfunction "2_2") (pintype "passive"))
    )
    (net (code "88") (name "unconnected-(J4-Pad1)") (class "Default")
      (node (ref "J4") (pin "1") (pinfunction "1_1") (pintype "passive"))
    )
    (net (code "89") (name "unconnected-(J4-Pad2)") (class "Default")
      (node (ref "J4") (pin "2") (pinfunction "2_2") (pintype "passive"))
    )
    (net (code "90") (name "unconnected-(Q1-C-Pad1)") (class "Default")
      (node (ref "Q1") (pin "1") (pinfunction "C_1") (pintype "passive"))
    )
    (net (code "91") (name "unconnected-(SV1-Pad22)") (class "Default")
      (node (ref "SV1") (pin "22") (pinfunction "22_22") (pintype "passive"))
    )
    (net (code "92") (name "unconnected-(SV1-Pad23)") (class "Default")
      (node (ref "SV1") (pin "23") (pinfunction "23_23") (pintype "passive"))
    )
    (net (code "93") (name "unconnected-(SV1-Pad24)") (class "Default")
      (node (ref "SV1") (pin "24") (pinfunction "24_24") (pintype "passive"))
    )
    (net (code "94") (name "unconnected-(TRIM1-E-Pad3)") (class "Default")
      (node (ref "TRIM1") (pin "3") (pinfunction "E_3") (pintype "passive"))
    )
    (net (code "95") (name "unconnected-(TRIM3-E-Pad3)") (class "Default")
      (node (ref "TRIM3") (pin "3") (pinfunction "E_3") (pintype "passive"))
    )
  )
)
